# MC_Cap_Sensing.net
KiCad netlist of a schematic drawn in Altium Designer
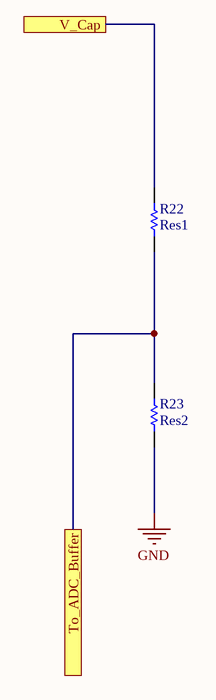
[diagram p0: MC_Cap_Sensing.SchDoc]

(export (version "E")
  (design (tool "Eeschema 10.0.6"))
  (components
    (comp (ref "R22")
      (value "Res1")
      (footprint "AXIAL-0.3")
      (description "Resistor")
      (fields (field (name "PUBLISHER") "Altium Limited"))
      (libsource (lib "Miscellaneous Devices") (part "Res1"))
    )
    (comp (ref "R23")
      (value "Res2")
      (footprint "AXIAL-0.3")
      (description "Resistor")
      (fields (field (name "PUBLISHER") "Altium Limited"))
      (libsource (lib "Miscellaneous Devices") (part "Res1"))
    )
  )
  (nets
    (net (code "1") (name "/To_ADC_Buffer") (class "Default")
      (node (ref "R22") (pin "1") (pinfunction "1_1") (pintype "passive"))
      (node (ref "R23") (pin "2") (pinfunction "2_2") (pintype "passive"))
    )
    (net (code "2") (name "/V_Cap") (class "Default")
      (node (ref "R22") (pin "2") (pinfunction "2_2") (pintype "passive"))
    )
    (net (code "3") (name "GND") (class "Default")
      (node (ref "R23") (pin "1") (pinfunction "1_1") (pintype "passive"))
    )
  )
)
